# 06-HDMI_KEY_MARK.net
KiCad netlist of a schematic drawn in Altium Designer
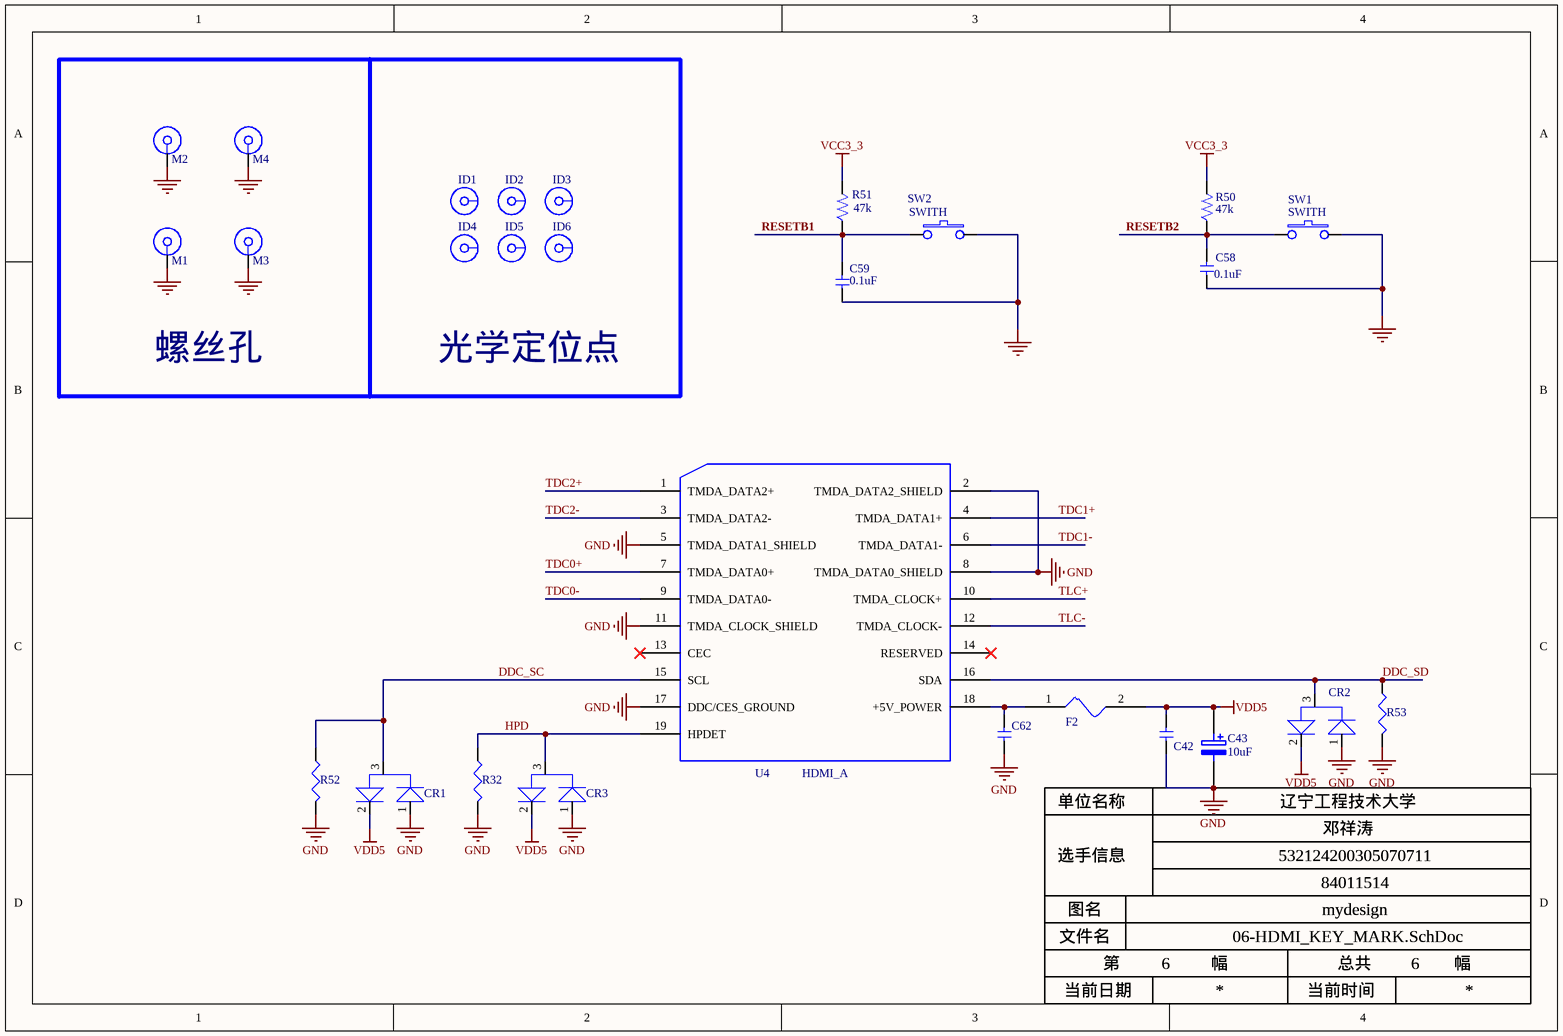
[diagram p0: 06-HDMI_KEY_MARK.SchDoc]

(export (version "E")
  (design (tool "Eeschema 10.0.6"))
  (components
    (comp (ref "C42")
      (value "C_2")
      (footprint "C0603")
      (fields (field (name "VOLTAGE") "CMAX"))
      (libsource (lib "sucaiku") (part "C_2"))
    )
    (comp (ref "C43")
      (value "10uF")
      (footprint "3528-C")
      (description "Electrolytic Capacitor")
      (libsource (lib "sucaiku") (part "ELECTRO2"))
    )
    (comp (ref "C58")
      (value "0.1uF")
      (footprint "C0603")
      (fields (field (name "VOLTAGE") "CMAX") (field (name "Comment") "C_2"))
      (libsource (lib "VIDEO_Demo_Kit_1") (part "C_2"))
    )
    (comp (ref "C59")
      (value "0.1uF")
      (footprint "C0603")
      (fields (field (name "VOLTAGE") "CMAX") (field (name "Comment") "C_2"))
      (libsource (lib "VIDEO_Demo_Kit_1") (part "C_2"))
    )
    (comp (ref "C62")
      (value "C_2")
      (footprint "C0603")
      (fields (field (name "VOLTAGE") "CMAX"))
      (libsource (lib "sucaiku") (part "C_2"))
    )
    (comp (ref "CR1")
      (value "DUALDIODE_1")
      (footprint "SOT-23")
      (libsource (lib "sucaiku") (part "DUALDIODE_1"))
    )
    (comp (ref "CR2")
      (value "DUALDIODE_1")
      (footprint "SOT-23")
      (libsource (lib "sucaiku") (part "DUALDIODE_1"))
    )
    (comp (ref "CR3")
      (value "DUALDIODE_1")
      (footprint "SOT-23")
      (libsource (lib "sucaiku") (part "DUALDIODE_1"))
    )
    (comp (ref "F2") (value "FUSE") (footprint "1206-F") (libsource (lib "sucaiku") (part "FUSE")))
    (comp (ref "ID1")
      (value "HO")
      (footprint "MARKS")
      (fields (field (name "SOURCE_PATH") "C:\\PROGRAM FILES\\印院出品\\CAPTURE 16.2\\LIBRARY\\CONNECTOR.OLB"))
      (libsource (lib "VIDEO_Demo_Kit_1") (part "BNC"))
    )
    (comp (ref "ID2")
      (value "HO")
      (footprint "MARKS")
      (fields (field (name "SOURCE_PATH") "C:\\PROGRAM FILES\\印院出品\\CAPTURE 16.2\\LIBRARY\\CONNECTOR.OLB"))
      (libsource (lib "VIDEO_Demo_Kit_1") (part "BNC"))
    )
    (comp (ref "ID3")
      (value "HO")
      (footprint "MARKS")
      (fields (field (name "SOURCE_PATH") "C:\\PROGRAM FILES\\印院出品\\CAPTURE 16.2\\LIBRARY\\CONNECTOR.OLB"))
      (libsource (lib "VIDEO_Demo_Kit_1") (part "BNC"))
    )
    (comp (ref "ID4")
      (value "HO")
      (footprint "MARKS")
      (fields (field (name "SOURCE_PATH") "C:\\PROGRAM FILES\\印院出品\\CAPTURE 16.2\\LIBRARY\\CONNECTOR.OLB"))
      (libsource (lib "VIDEO_Demo_Kit_1") (part "BNC"))
    )
    (comp (ref "ID5")
      (value "HO")
      (footprint "MARKS")
      (fields (field (name "SOURCE_PATH") "C:\\PROGRAM FILES\\印院出品\\CAPTURE 16.2\\LIBRARY\\CONNECTOR.OLB"))
      (libsource (lib "VIDEO_Demo_Kit_1") (part "BNC"))
    )
    (comp (ref "ID6")
      (value "HO")
      (footprint "MARKS")
      (fields (field (name "SOURCE_PATH") "C:\\PROGRAM FILES\\印院出品\\CAPTURE 16.2\\LIBRARY\\CONNECTOR.OLB"))
      (libsource (lib "VIDEO_Demo_Kit_1") (part "BNC"))
    )
    (comp (ref "M1")
      (value "HO")
      (footprint "MOUNT")
      (fields (field (name "SOURCE_PATH") "C:\\PROGRAM FILES\\印院出品\\CAPTURE 16.2\\LIBRARY\\CONNECTOR.OLB"))
      (libsource (lib "") (part "BNC_1"))
    )
    (comp (ref "M2")
      (value "HO")
      (footprint "MOUNT")
      (fields (field (name "SOURCE_PATH") "C:\\PROGRAM FILES\\印院出品\\CAPTURE 16.2\\LIBRARY\\CONNECTOR.OLB"))
      (libsource (lib "") (part "BNC_1"))
    )
    (comp (ref "M3")
      (value "HO")
      (footprint "MOUNT")
      (fields (field (name "SOURCE_PATH") "C:\\PROGRAM FILES\\印院出品\\CAPTURE 16.2\\LIBRARY\\CONNECTOR.OLB"))
      (libsource (lib "") (part "BNC_1"))
    )
    (comp (ref "M4")
      (value "HO")
      (footprint "MOUNT")
      (fields (field (name "SOURCE_PATH") "C:\\PROGRAM FILES\\印院出品\\CAPTURE 16.2\\LIBRARY\\CONNECTOR.OLB"))
      (libsource (lib "") (part "BNC_1"))
    )
    (comp (ref "R32") (value "R") (footprint "R0603") (libsource (lib "sucaiku") (part "R")))
    (comp (ref "R50")
      (value "47k")
      (footprint "R0603")
      (fields (field (name "POWER") "RMAX") (field (name "VOLTAGE") "RVMAX") (field (name "Comment") "R_3"))
      (libsource (lib "VIDEO_Demo_Kit_1") (part "R_3"))
    )
    (comp (ref "R51")
      (value "47k")
      (footprint "R0603")
      (fields (field (name "POWER") "RMAX") (field (name "VOLTAGE") "RVMAX") (field (name "Comment") "R_3"))
      (libsource (lib "VIDEO_Demo_Kit_1") (part "R_3"))
    )
    (comp (ref "R52") (value "R") (footprint "R0603") (libsource (lib "sucaiku") (part "R")))
    (comp (ref "R53") (value "R") (footprint "R0603") (libsource (lib "sucaiku") (part "R")))
    (comp (ref "SW1")
      (value "SWITH")
      (footprint "SW-280")
      (fields (field (name "Comment") "SW_PUSHBUTTON_2"))
      (libsource (lib "VIDEO_Demo_Kit_1") (part "SW_PUSHBUTTON_2"))
    )
    (comp (ref "SW2")
      (value "SWITH")
      (footprint "SW-280")
      (fields (field (name "Comment") "SW_PUSHBUTTON_2"))
      (libsource (lib "VIDEO_Demo_Kit_1") (part "SW_PUSHBUTTON_2"))
    )
    (comp (ref "U4") (value "HDMI_A") (footprint "HDMI_A") (libsource (lib "84011514") (part "HDMI_A")))
  )
  (nets
    (net (code "1") (name "/DDC_SC") (class "Default")
      (node (ref "CR1") (pin "3") (pinfunction "3_3") (pintype "passive"))
      (node (ref "R52") (pin "1") (pinfunction "1_1") (pintype "passive"))
      (node (ref "U4") (pin "15") (pinfunction "SCL_15") (pintype "passive"))
    )
    (net (code "2") (name "/DDC_SD") (class "Default")
      (node (ref "CR2") (pin "3") (pinfunction "3_3") (pintype "passive"))
      (node (ref "R53") (pin "1") (pinfunction "1_1") (pintype "passive"))
      (node (ref "U4") (pin "16") (pinfunction "SDA_16") (pintype "passive"))
    )
    (net (code "3") (name "/HPD") (class "Default")
      (node (ref "CR3") (pin "3") (pinfunction "3_3") (pintype "passive"))
      (node (ref "R32") (pin "1") (pinfunction "1_1") (pintype "passive"))
      (node (ref "U4") (pin "19") (pinfunction "HPDET_19") (pintype "passive"))
    )
    (net (code "4") (name "/RESETB1") (class "Default")
      (node (ref "C59") (pin "2") (pinfunction "2_2") (pintype "passive"))
      (node (ref "R51") (pin "1") (pinfunction "1_1") (pintype "passive"))
      (node (ref "SW2") (pin "1") (pinfunction "1_1") (pintype "passive"))
    )
    (net (code "5") (name "/RESETB2") (class "Default")
      (node (ref "C58") (pin "2") (pinfunction "2_2") (pintype "passive"))
      (node (ref "R50") (pin "1") (pinfunction "1_1") (pintype "passive"))
      (node (ref "SW1") (pin "1") (pinfunction "1_1") (pintype "passive"))
    )
    (net (code "6") (name "/TDC0+") (class "Default")
      (node (ref "U4") (pin "7") (pinfunction "TMDA_DATA0+_7") (pintype "passive"))
    )
    (net (code "7") (name "/TDC0-") (class "Default")
      (node (ref "U4") (pin "9") (pinfunction "TMDA_DATA0-_9") (pintype "passive"))
    )
    (net (code "8") (name "/TDC1+") (class "Default")
      (node (ref "U4") (pin "4") (pinfunction "TMDA_DATA1+_4") (pintype "passive"))
    )
    (net (code "9") (name "/TDC1-") (class "Default")
      (node (ref "U4") (pin "6") (pinfunction "TMDA_DATA1-_6") (pintype "passive"))
    )
    (net (code "10") (name "/TDC2+") (class "Default")
      (node (ref "U4") (pin "1") (pinfunction "TMDA_DATA2+_1") (pintype "passive"))
    )
    (net (code "11") (name "/TDC2-") (class "Default")
      (node (ref "U4") (pin "3") (pinfunction "TMDA_DATA2-_3") (pintype "passive"))
    )
    (net (code "12") (name "/TLC+") (class "Default")
      (node (ref "U4") (pin "10") (pinfunction "TMDA_CLOCK+_10") (pintype "passive"))
    )
    (net (code "13") (name "/TLC-") (class "Default")
      (node (ref "U4") (pin "12") (pinfunction "TMDA_CLOCK-_12") (pintype "passive"))
    )
    (net (code "14") (name "GND") (class "Default")
      (node (ref "C42") (pin "1") (pinfunction "1_1") (pintype "passive"))
      (node (ref "C43") (pin "2") (pinfunction "2_2") (pintype "passive"))
      (node (ref "C58") (pin "1") (pinfunction "1_1") (pintype "passive"))
      (node (ref "C59") (pin "1") (pinfunction "1_1") (pintype "passive"))
      (node (ref "C62") (pin "1") (pinfunction "1_1") (pintype "passive"))
      (node (ref "CR1") (pin "1") (pinfunction "1_1") (pintype "passive"))
      (node (ref "CR2") (pin "1") (pinfunction "1_1") (pintype "passive"))
      (node (ref "CR3") (pin "1") (pinfunction "1_1") (pintype "passive"))
      (node (ref "M1") (pin "1") (pinfunction "1_1") (pintype "passive"))
      (node (ref "M2") (pin "1") (pinfunction "1_1") (pintype "passive"))
      (node (ref "M3") (pin "1") (pinfunction "1_1") (pintype "passive"))
      (node (ref "M4") (pin "1") (pinfunction "1_1") (pintype "passive"))
      (node (ref "R32") (pin "2") (pinfunction "2_2") (pintype "passive"))
      (node (ref "R52") (pin "2") (pinfunction "2_2") (pintype "passive"))
      (node (ref "R53") (pin "2") (pinfunction "2_2") (pintype "passive"))
      (node (ref "SW1") (pin "2") (pinfunction "2_2") (pintype "passive"))
      (node (ref "SW2") (pin "2") (pinfunction "2_2") (pintype "passive"))
      (node (ref "U4") (pin "11") (pinfunction "TMDA_CLOCK_SHIELD_11") (pintype "passive"))
      (node (ref "U4") (pin "17") (pinfunction "DDC/CES_GROUND_17") (pintype "passive"))
      (node (ref "U4") (pin "2") (pinfunction "TMDA_DATA2_SHIELD_2") (pintype "passive"))
      (node (ref "U4") (pin "5") (pinfunction "TMDA_DATA1_SHIELD_5") (pintype "passive"))
      (node (ref "U4") (pin "8") (pinfunction "TMDA_DATA0_SHIELD_8") (pintype "passive"))
    )
    (net (code "15") (name "Net-(U4-+5V_POWER)") (class "Default")
      (node (ref "C62") (pin "2") (pinfunction "2_2") (pintype "passive"))
      (node (ref "F2") (pin "1") (pinfunction "1_1") (pintype "passive"))
      (node (ref "U4") (pin "18") (pinfunction "+5V_POWER_18") (pintype "passive"))
    )
    (net (code "16") (name "VCC3_3") (class "Default")
      (node (ref "R50") (pin "2") (pinfunction "2_2") (pintype "passive"))
      (node (ref "R51") (pin "2") (pinfunction "2_2") (pintype "passive"))
    )
    (net (code "17") (name "VDD5") (class "Default")
      (node (ref "C42") (pin "2") (pinfunction "2_2") (pintype "passive"))
      (node (ref "C43") (pin "1") (pinfunction "1_1") (pintype "passive"))
      (node (ref "CR1") (pin "2") (pinfunction "2_2") (pintype "passive"))
      (node (ref "CR2") (pin "2") (pinfunction "2_2") (pintype "passive"))
      (node (ref "CR3") (pin "2") (pinfunction "2_2") (pintype "passive"))
      (node (ref "F2") (pin "2") (pinfunction "2_2") (pintype "passive"))
    )
    (net (code "18") (name "unconnected-(U4-CEC-Pad13)") (class "Default")
      (node (ref "U4") (pin "13") (pinfunction "CEC_13") (pintype "passive+no_connect"))
    )
    (net (code "19") (name "unconnected-(U4-RESERVED-Pad14)") (class "Default")
      (node (ref "U4") (pin "14") (pinfunction "RESERVED_14") (pintype "passive+no_connect"))
    )
  )
)
